# Video.net
KiCad netlist of a schematic drawn in Altium Designer
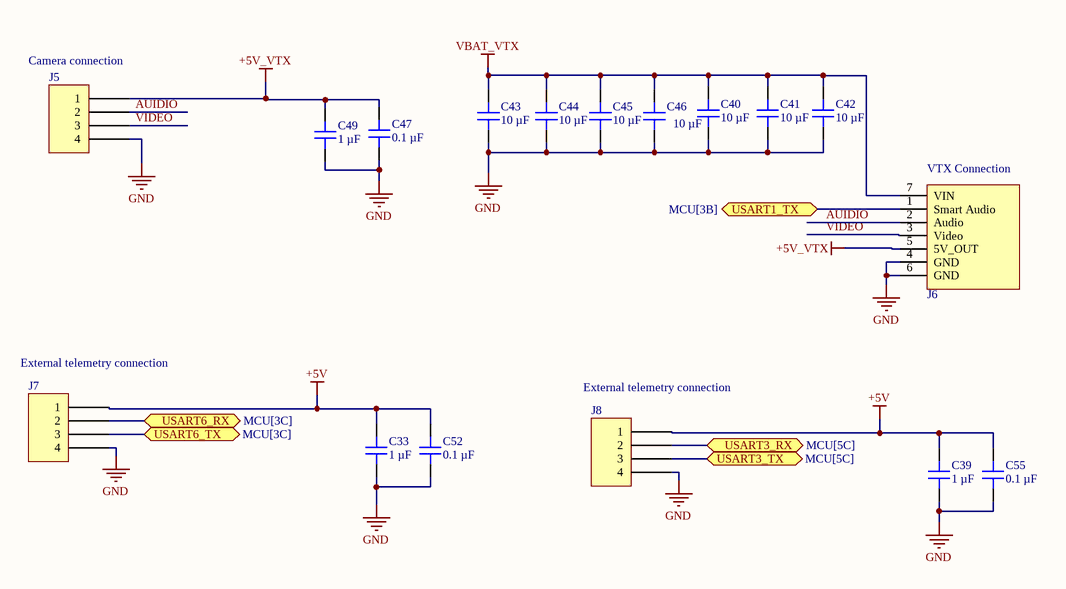
[diagram p0: Video.SchDoc]

(export (version "E")
  (design (tool "Eeschema 10.0.6"))
  (components
    (comp (ref "C33")
      (value "1 µF")
      (footprint "CAP 0402_1005")
      (description "CAP0402 X7R 1UF 10% 6.3V")
      (fields
        (field (name "PART NUMBER") "GMC04X7R105K6R3NT")
        (field (name "CAPACITANCE") "1 µF")
        (field (name "MANUFACTURER") "Cal-Chip Electronics, Inc.")
      )
      (libsource (lib "Celestial Altium Library - altium_library") (part "Capacitor"))
    )
    (comp (ref "C39")
      (value "1 µF")
      (footprint "CAP 0402_1005")
      (description "CAP0402 X7R 1UF 10% 6.3V")
      (fields
        (field (name "PART NUMBER") "GMC04X7R105K6R3NT")
        (field (name "CAPACITANCE") "1 µF")
        (field (name "MANUFACTURER") "Cal-Chip Electronics, Inc.")
      )
      (libsource (lib "Celestial Altium Library - altium_library") (part "Capacitor"))
    )
    (comp (ref "C40")
      (value "10 µF")
      (footprint "MURATA GRM188 0603_1608")
      (description "CAP CER 10UF 25V X5R 0603")
      (fields
        (field (name "PART NUMBER") "GRM188R61E106KA73D")
        (field (name "CAPACITANCE") "10 µF")
        (field (name "MANUFACTURER") "Murata Electronics")
      )
      (libsource (lib "Celestial Altium Library - altium_library") (part "Capacitor"))
    )
    (comp (ref "C41")
      (value "10 µF")
      (footprint "MURATA GRM188 0603_1608")
      (description "CAP CER 10UF 25V X5R 0603")
      (fields
        (field (name "PART NUMBER") "GRM188R61E106KA73D")
        (field (name "CAPACITANCE") "10 µF")
        (field (name "MANUFACTURER") "Murata Electronics")
      )
      (libsource (lib "Celestial Altium Library - altium_library") (part "Capacitor"))
    )
    (comp (ref "C42")
      (value "10 µF")
      (footprint "MURATA GRM188 0603_1608")
      (description "CAP CER 10UF 25V X5R 0603")
      (fields
        (field (name "PART NUMBER") "GRM188R61E106KA73D")
        (field (name "CAPACITANCE") "10 µF")
        (field (name "MANUFACTURER") "Murata Electronics")
      )
      (libsource (lib "Celestial Altium Library - altium_library") (part "Capacitor"))
    )
    (comp (ref "C43")
      (value "10 µF")
      (footprint "MURATA GRM188 0603_1608")
      (description "CAP CER 10UF 25V X5R 0603")
      (fields
        (field (name "PART NUMBER") "GRM188R61E106KA73D")
        (field (name "CAPACITANCE") "10 µF")
        (field (name "MANUFACTURER") "Murata Electronics")
      )
      (libsource (lib "Celestial Altium Library - altium_library") (part "Capacitor"))
    )
    (comp (ref "C44")
      (value "10 µF")
      (footprint "MURATA GRM188 0603_1608")
      (description "CAP CER 10UF 25V X5R 0603")
      (fields
        (field (name "PART NUMBER") "GRM188R61E106KA73D")
        (field (name "CAPACITANCE") "10 µF")
        (field (name "MANUFACTURER") "Murata Electronics")
      )
      (libsource (lib "Celestial Altium Library - altium_library") (part "Capacitor"))
    )
    (comp (ref "C45")
      (value "10 µF")
      (footprint "MURATA GRM188 0603_1608")
      (description "CAP CER 10UF 25V X5R 0603")
      (fields
        (field (name "PART NUMBER") "GRM188R61E106KA73D")
        (field (name "CAPACITANCE") "10 µF")
        (field (name "MANUFACTURER") "Murata Electronics")
      )
      (libsource (lib "Celestial Altium Library - altium_library") (part "Capacitor"))
    )
    (comp (ref "C46")
      (value "10 µF")
      (footprint "MURATA GRM188 0603_1608")
      (description "CAP CER 10UF 25V X5R 0603")
      (fields
        (field (name "PART NUMBER") "GRM188R61E106KA73D")
        (field (name "CAPACITANCE") "10 µF")
        (field (name "MANUFACTURER") "Murata Electronics")
      )
      (libsource (lib "Celestial Altium Library - altium_library") (part "Capacitor"))
    )
    (comp (ref "C47")
      (value "0.1 µF")
      (footprint "CAP 0402_1005")
      (description "CAP CER 0.1UF 6.3V X5R 0402")
      (fields
        (field (name "PART NUMBER") "CC0402MRX5R5BB104")
        (field (name "CAPACITANCE") "0.1 µF")
        (field (name "MANUFACTURER") "Yageo")
      )
      (libsource (lib "Celestial Altium Library - altium_library") (part "Capacitor"))
    )
    (comp (ref "C49")
      (value "1 µF")
      (footprint "CAP 0402_1005")
      (description "CAP0402 X7R 1UF 10% 6.3V")
      (fields
        (field (name "PART NUMBER") "GMC04X7R105K6R3NT")
        (field (name "CAPACITANCE") "1 µF")
        (field (name "MANUFACTURER") "Cal-Chip Electronics, Inc.")
      )
      (libsource (lib "Celestial Altium Library - altium_library") (part "Capacitor"))
    )
    (comp (ref "C52")
      (value "0.1 µF")
      (footprint "CAP 0402_1005")
      (description "CAP CER 0.1UF 6.3V X5R 0402")
      (fields
        (field (name "PART NUMBER") "CC0402MRX5R5BB104")
        (field (name "CAPACITANCE") "0.1 µF")
        (field (name "MANUFACTURER") "Yageo")
      )
      (libsource (lib "Celestial Altium Library - altium_library") (part "Capacitor"))
    )
    (comp (ref "C55")
      (value "0.1 µF")
      (footprint "CAP 0402_1005")
      (description "CAP CER 0.1UF 6.3V X5R 0402")
      (fields
        (field (name "PART NUMBER") "CC0402MRX5R5BB104")
        (field (name "CAPACITANCE") "0.1 µF")
        (field (name "MANUFACTURER") "Yageo")
      )
      (libsource (lib "Celestial Altium Library - altium_library") (part "Capacitor"))
    )
    (comp (ref "J5")
      (value "DF13A-4P-1.25H(75)")
      (footprint "HIROSE DF13A-4P-1.25H")
      (description "CONN HEADER SMD R/A 4POS 1MM")
      (fields
        (field (name "PART NUMBER") "SM04B-SRSS-TB(LF)(SN)")
        (field (name "MANUFACTURER") "JST Sales America Inc.")
      )
      (libsource (lib "Celestial Altium Library - altium_library") (part "4 Pin"))
    )
    (comp (ref "J6")
      (value "TBS Unify PRO32 HV 5G8")
      (footprint "TBS Unify Pro 5G8 HV Race")
      (description "Video transmitter")
      (libsource (lib "PCB_Lib") (part "TBS Unify PRO32 HV 5G8"))
    )
    (comp (ref "J7")
      (value "DF13A-4P-1.25H(75)")
      (footprint "HIROSE DF13A-4P-1.25H")
      (description "CONN HEADER SMD R/A 4POS 1MM")
      (fields
        (field (name "PART NUMBER") "SM04B-SRSS-TB(LF)(SN)")
        (field (name "MANUFACTURER") "JST Sales America Inc.")
      )
      (libsource (lib "Celestial Altium Library - altium_library") (part "4 Pin"))
    )
    (comp (ref "J8")
      (value "DF13A-4P-1.25H(75)")
      (footprint "HIROSE DF13A-4P-1.25H")
      (description "CONN HEADER SMD R/A 4POS 1MM")
      (fields
        (field (name "PART NUMBER") "SM04B-SRSS-TB(LF)(SN)")
        (field (name "MANUFACTURER") "JST Sales America Inc.")
      )
      (libsource (lib "Celestial Altium Library - altium_library") (part "4 Pin"))
    )
  )
  (nets
    (net (code "1") (name "+5V") (class "Default")
      (node (ref "C33") (pin "2") (pinfunction "2_2") (pintype "passive"))
      (node (ref "C39") (pin "2") (pinfunction "2_2") (pintype "passive"))
      (node (ref "C52") (pin "2") (pinfunction "2_2") (pintype "passive"))
      (node (ref "C55") (pin "2") (pinfunction "2_2") (pintype "passive"))
      (node (ref "J7") (pin "1") (pinfunction "1_1") (pintype "passive"))
      (node (ref "J8") (pin "1") (pinfunction "1_1") (pintype "passive"))
    )
    (net (code "2") (name "+5V_VTX") (class "Default")
      (node (ref "C47") (pin "2") (pinfunction "2_2") (pintype "passive"))
      (node (ref "C49") (pin "2") (pinfunction "2_2") (pintype "passive"))
      (node (ref "J5") (pin "1") (pinfunction "1_1") (pintype "passive"))
      (node (ref "J6") (pin "5") (pinfunction "5V_OUT_5") (pintype "passive"))
    )
    (net (code "3") (name "/AUIDIO") (class "Default")
      (node (ref "J5") (pin "2") (pinfunction "2_2") (pintype "passive"))
      (node (ref "J6") (pin "2") (pinfunction "Audio_2") (pintype "passive"))
    )
    (net (code "4") (name "/USART1_TX") (class "Default")
      (node (ref "J6") (pin "1") (pinfunction "Smart_Audio_1") (pintype "passive"))
    )
    (net (code "5") (name "/USART3_RX") (class "Default")
      (node (ref "J8") (pin "2") (pinfunction "2_2") (pintype "passive"))
    )
    (net (code "6") (name "/USART3_TX") (class "Default")
      (node (ref "J8") (pin "3") (pinfunction "3_3") (pintype "passive"))
    )
    (net (code "7") (name "/USART6_RX") (class "Default")
      (node (ref "J7") (pin "2") (pinfunction "2_2") (pintype "passive"))
    )
    (net (code "8") (name "/USART6_TX") (class "Default")
      (node (ref "J7") (pin "3") (pinfunction "3_3") (pintype "passive"))
    )
    (net (code "9") (name "/VIDEO") (class "Default")
      (node (ref "J5") (pin "3") (pinfunction "3_3") (pintype "passive"))
      (node (ref "J6") (pin "3") (pinfunction "Video_3") (pintype "passive"))
    )
    (net (code "10") (name "GND") (class "Default")
      (node (ref "C33") (pin "1") (pinfunction "1_1") (pintype "passive"))
      (node (ref "C39") (pin "1") (pinfunction "1_1") (pintype "passive"))
      (node (ref "C40") (pin "1") (pinfunction "1_1") (pintype "passive"))
      (node (ref "C41") (pin "1") (pinfunction "1_1") (pintype "passive"))
      (node (ref "C42") (pin "1") (pinfunction "1_1") (pintype "passive"))
      (node (ref "C43") (pin "1") (pinfunction "1_1") (pintype "passive"))
      (node (ref "C44") (pin "1") (pinfunction "1_1") (pintype "passive"))
      (node (ref "C45") (pin "1") (pinfunction "1_1") (pintype "passive"))
      (node (ref "C46") (pin "1") (pinfunction "1_1") (pintype "passive"))
      (node (ref "C47") (pin "1") (pinfunction "1_1") (pintype "passive"))
      (node (ref "C49") (pin "1") (pinfunction "1_1") (pintype "passive"))
      (node (ref "C52") (pin "1") (pinfunction "1_1") (pintype "passive"))
      (node (ref "C55") (pin "1") (pinfunction "1_1") (pintype "passive"))
      (node (ref "J5") (pin "4") (pinfunction "4_4") (pintype "passive"))
      (node (ref "J6") (pin "4") (pinfunction "GND_4") (pintype "passive"))
      (node (ref "J6") (pin "6") (pinfunction "GND_6") (pintype "passive"))
      (node (ref "J7") (pin "4") (pinfunction "4_4") (pintype "passive"))
      (node (ref "J8") (pin "4") (pinfunction "4_4") (pintype "passive"))
    )
    (net (code "11") (name "VBAT_VTX") (class "Default")
      (node (ref "C40") (pin "2") (pinfunction "2_2") (pintype "passive"))
      (node (ref "C41") (pin "2") (pinfunction "2_2") (pintype "passive"))
      (node (ref "C42") (pin "2") (pinfunction "2_2") (pintype "passive"))
      (node (ref "C43") (pin "2") (pinfunction "2_2") (pintype "passive"))
      (node (ref "C44") (pin "2") (pinfunction "2_2") (pintype "passive"))
      (node (ref "C45") (pin "2") (pinfunction "2_2") (pintype "passive"))
      (node (ref "C46") (pin "2") (pinfunction "2_2") (pintype "passive"))
      (node (ref "J6") (pin "7") (pinfunction "VIN_7") (pintype "passive"))
    )
  )
)
